# AVerCADE.net
KiCad netlist of a schematic drawn in EAGLE
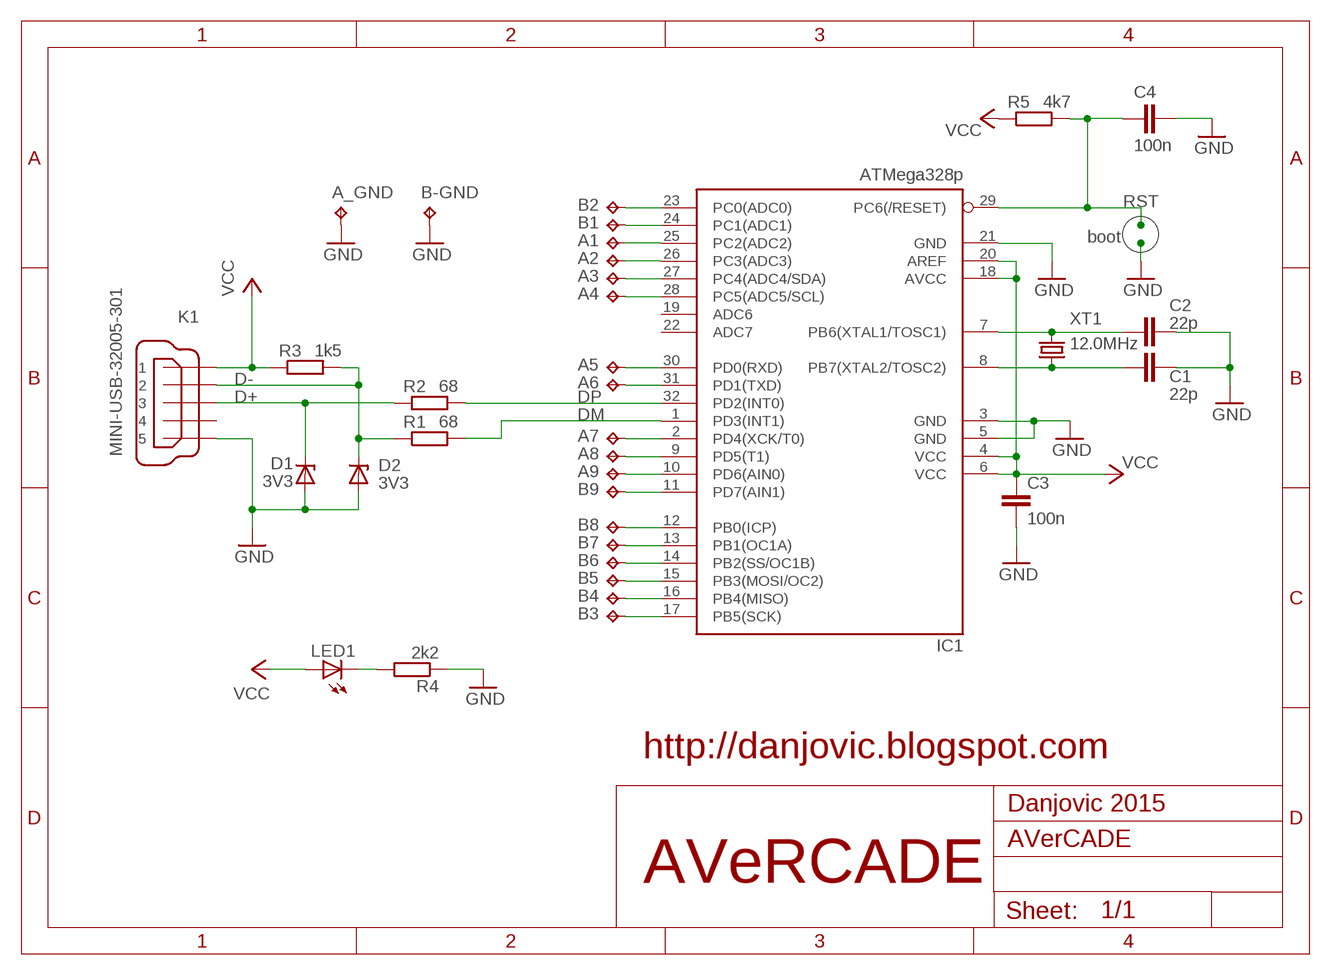
[diagram p0: schematic, sheet 1]

(export (version "E")
  (design (tool "Eeschema 10.0.6"))
  (components
    (comp (ref "A1")
      (value "TPPAD1-13")
      (footprint "eagle-import:P1-13")
      (libsource (lib "eagle-import") (part "TPPAD1-13"))
    )
    (comp (ref "A2")
      (value "TPPAD1-13")
      (footprint "eagle-import:P1-13")
      (libsource (lib "eagle-import") (part "TPPAD1-13"))
    )
    (comp (ref "A3")
      (value "TPPAD1-13")
      (footprint "eagle-import:P1-13")
      (libsource (lib "eagle-import") (part "TPPAD1-13"))
    )
    (comp (ref "A4")
      (value "TPPAD1-13")
      (footprint "eagle-import:P1-13")
      (libsource (lib "eagle-import") (part "TPPAD1-13"))
    )
    (comp (ref "A5")
      (value "TPPAD1-13")
      (footprint "eagle-import:P1-13")
      (libsource (lib "eagle-import") (part "TPPAD1-13"))
    )
    (comp (ref "A6")
      (value "TPPAD1-13")
      (footprint "eagle-import:P1-13")
      (libsource (lib "eagle-import") (part "TPPAD1-13"))
    )
    (comp (ref "A7")
      (value "TPPAD1-13")
      (footprint "eagle-import:P1-13")
      (libsource (lib "eagle-import") (part "TPPAD1-13"))
    )
    (comp (ref "A8")
      (value "TPPAD1-13")
      (footprint "eagle-import:P1-13")
      (libsource (lib "eagle-import") (part "TPPAD1-13"))
    )
    (comp (ref "A9")
      (value "TPPAD1-13")
      (footprint "eagle-import:P1-13")
      (libsource (lib "eagle-import") (part "TPPAD1-13"))
    )
    (comp (ref "A_GND")
      (value "TPPAD1-13")
      (footprint "eagle-import:P1-13")
      (libsource (lib "eagle-import") (part "TPPAD1-13"))
    )
    (comp (ref "B-GND")
      (value "TPPAD1-13")
      (footprint "eagle-import:P1-13")
      (libsource (lib "eagle-import") (part "TPPAD1-13"))
    )
    (comp (ref "B1")
      (value "TPPAD1-13")
      (footprint "eagle-import:P1-13")
      (libsource (lib "eagle-import") (part "TPPAD1-13"))
    )
    (comp (ref "B2")
      (value "TPPAD1-13")
      (footprint "eagle-import:P1-13")
      (libsource (lib "eagle-import") (part "TPPAD1-13"))
    )
    (comp (ref "B3")
      (value "TPPAD1-13")
      (footprint "eagle-import:P1-13")
      (libsource (lib "eagle-import") (part "TPPAD1-13"))
    )
    (comp (ref "B4")
      (value "TPPAD1-13")
      (footprint "eagle-import:P1-13")
      (libsource (lib "eagle-import") (part "TPPAD1-13"))
    )
    (comp (ref "B5")
      (value "TPPAD1-13")
      (footprint "eagle-import:P1-13")
      (libsource (lib "eagle-import") (part "TPPAD1-13"))
    )
    (comp (ref "B6")
      (value "TPPAD1-13")
      (footprint "eagle-import:P1-13")
      (libsource (lib "eagle-import") (part "TPPAD1-13"))
    )
    (comp (ref "B7")
      (value "TPPAD1-13")
      (footprint "eagle-import:P1-13")
      (libsource (lib "eagle-import") (part "TPPAD1-13"))
    )
    (comp (ref "B8")
      (value "TPPAD1-13")
      (footprint "eagle-import:P1-13")
      (libsource (lib "eagle-import") (part "TPPAD1-13"))
    )
    (comp (ref "B9")
      (value "TPPAD1-13")
      (footprint "eagle-import:P1-13")
      (libsource (lib "eagle-import") (part "TPPAD1-13"))
    )
    (comp (ref "C1")
      (value "22p")
      (footprint "eagle-import:C0805")
      (libsource (lib "eagle-import") (part "C-EUC0805"))
    )
    (comp (ref "C2")
      (value "22p")
      (footprint "eagle-import:C0805")
      (libsource (lib "eagle-import") (part "C-EUC0805"))
    )
    (comp (ref "C3")
      (value "100n")
      (footprint "eagle-import:C1206")
      (libsource (lib "eagle-import") (part "C-EUC1206"))
    )
    (comp (ref "C4")
      (value "100n")
      (footprint "eagle-import:C1206")
      (libsource (lib "eagle-import") (part "C-EUC1206"))
    )
    (comp (ref "D1")
      (value "3V3")
      (footprint "eagle-import:SOD80C")
      (libsource (lib "eagle-import") (part "ZENER-DIODESOD80C"))
    )
    (comp (ref "D2")
      (value "3V3")
      (footprint "eagle-import:SOD80C")
      (libsource (lib "eagle-import") (part "ZENER-DIODESOD80C"))
    )
    (comp (ref "IC1")
      (value "ATMega328p")
      (footprint "eagle-import:TQFP32-08")
      (fields (field (name "MPN") "ATMEGA8-16AU"))
      (libsource (lib "eagle-import") (part "MEGA8-AI"))
    )
    (comp (ref "K1")
      (value "MINI-USB-32005-301")
      (footprint "eagle-import:32005-301")
      (libsource (lib "eagle-import") (part "MINI-USB-32005-301"))
    )
    (comp (ref "LED1")
      (value "LEDSML1206")
      (footprint "eagle-import:SML1206")
      (libsource (lib "eagle-import") (part "LEDSML1206"))
    )
    (comp (ref "R1")
      (value "68")
      (footprint "eagle-import:M1206")
      (libsource (lib "eagle-import") (part "R-EU_M1206"))
    )
    (comp (ref "R2")
      (value "68")
      (footprint "eagle-import:M1206")
      (libsource (lib "eagle-import") (part "R-EU_M1206"))
    )
    (comp (ref "R3")
      (value "1k5")
      (footprint "eagle-import:M1206")
      (libsource (lib "eagle-import") (part "R-EU_M1206"))
    )
    (comp (ref "R4")
      (value "2k2")
      (footprint "eagle-import:M1206")
      (libsource (lib "eagle-import") (part "R-EU_M1206"))
    )
    (comp (ref "R5")
      (value "4k7")
      (footprint "eagle-import:M1206")
      (libsource (lib "eagle-import") (part "R-EU_M1206"))
    )
    (comp (ref "XT1")
      (value "12.0MHz")
      (footprint "eagle-import:HC49UP")
      (libsource (lib "eagle-import") (part "CRYSTALHC49UP"))
    )
  )
  (nets
    (net (code "1") (name "/D+") (class "Default")
      (node (ref "D1") (pin "C") (pinfunction "C_C") (pintype "passive"))
      (node (ref "K1") (pin "3") (pinfunction "3_3") (pintype "passive"))
      (node (ref "R2") (pin "1") (pinfunction "1_1") (pintype "passive"))
    )
    (net (code "2") (name "/D-") (class "Default")
      (node (ref "D2") (pin "C") (pinfunction "C_C") (pintype "passive"))
      (node (ref "K1") (pin "2") (pinfunction "2_2") (pintype "passive"))
      (node (ref "R1") (pin "1") (pinfunction "1_1") (pintype "passive"))
      (node (ref "R3") (pin "2") (pinfunction "2_2") (pintype "passive"))
    )
    (net (code "3") (name "/DM") (class "Default")
      (node (ref "IC1") (pin "1") (pinfunction "PD3(INT1)_1") (pintype "bidirectional"))
      (node (ref "R1") (pin "2") (pinfunction "2_2") (pintype "passive"))
    )
    (net (code "4") (name "/DP") (class "Default")
      (node (ref "IC1") (pin "32") (pinfunction "PD2(INT0)_32") (pintype "bidirectional"))
      (node (ref "R2") (pin "2") (pinfunction "2_2") (pintype "passive"))
    )
    (net (code "5") (name "/RST") (class "Default")
      (node (ref "C4") (pin "1") (pinfunction "1_1") (pintype "passive"))
      (node (ref "IC1") (pin "29") (pinfunction "PC6(/RESET)_29") (pintype "bidirectional"))
      (node (ref "R5") (pin "2") (pinfunction "2_2") (pintype "passive"))
    )
    (net (code "6") (name "GND") (class "Default")
      (node (ref "A_GND") (pin "TP") (pinfunction "TP_TP") (pintype "input"))
      (node (ref "B-GND") (pin "TP") (pinfunction "TP_TP") (pintype "input"))
      (node (ref "C1") (pin "2") (pinfunction "2_2") (pintype "passive"))
      (node (ref "C2") (pin "2") (pinfunction "2_2") (pintype "passive"))
      (node (ref "C3") (pin "2") (pinfunction "2_2") (pintype "passive"))
      (node (ref "C4") (pin "2") (pinfunction "2_2") (pintype "passive"))
      (node (ref "D1") (pin "A") (pinfunction "A_A") (pintype "passive"))
      (node (ref "D2") (pin "A") (pinfunction "A_A") (pintype "passive"))
      (node (ref "IC1") (pin "21") (pinfunction "GND_21") (pintype "power_in"))
      (node (ref "IC1") (pin "3") (pinfunction "GND_3") (pintype "power_in"))
      (node (ref "IC1") (pin "5") (pinfunction "GND_5") (pintype "power_in"))
      (node (ref "K1") (pin "5") (pinfunction "5_5") (pintype "passive"))
      (node (ref "R4") (pin "1") (pinfunction "1_1") (pintype "passive"))
    )
    (net (code "7") (name "Net-(IC1-PB0(ICP))") (class "Default")
      (node (ref "B8") (pin "TP") (pinfunction "TP_TP") (pintype "input"))
      (node (ref "IC1") (pin "12") (pinfunction "PB0(ICP)_12") (pintype "bidirectional"))
    )
    (net (code "8") (name "Net-(IC1-PB1(OC1A))") (class "Default")
      (node (ref "B7") (pin "TP") (pinfunction "TP_TP") (pintype "input"))
      (node (ref "IC1") (pin "13") (pinfunction "PB1(OC1A)_13") (pintype "bidirectional"))
    )
    (net (code "9") (name "Net-(IC1-PB2(SS{slash}OC1B))") (class "Default")
      (node (ref "B6") (pin "TP") (pinfunction "TP_TP") (pintype "input"))
      (node (ref "IC1") (pin "14") (pinfunction "PB2(SS/OC1B)_14") (pintype "bidirectional"))
    )
    (net (code "10") (name "Net-(IC1-PB3(MOSI{slash}OC2))") (class "Default")
      (node (ref "B5") (pin "TP") (pinfunction "TP_TP") (pintype "input"))
      (node (ref "IC1") (pin "15") (pinfunction "PB3(MOSI/OC2)_15") (pintype "bidirectional"))
    )
    (net (code "11") (name "Net-(IC1-PB4(MISO))") (class "Default")
      (node (ref "B4") (pin "TP") (pinfunction "TP_TP") (pintype "input"))
      (node (ref "IC1") (pin "16") (pinfunction "PB4(MISO)_16") (pintype "bidirectional"))
    )
    (net (code "12") (name "Net-(IC1-PB5(SCK))") (class "Default")
      (node (ref "B3") (pin "TP") (pinfunction "TP_TP") (pintype "input"))
      (node (ref "IC1") (pin "17") (pinfunction "PB5(SCK)_17") (pintype "bidirectional"))
    )
    (net (code "13") (name "Net-(IC1-PB6(XTAL1{slash}TOSC1))") (class "Default")
      (node (ref "C2") (pin "1") (pinfunction "1_1") (pintype "passive"))
      (node (ref "IC1") (pin "7") (pinfunction "PB6(XTAL1/TOSC1)_7") (pintype "bidirectional"))
      (node (ref "XT1") (pin "2") (pinfunction "2_2") (pintype "passive"))
    )
    (net (code "14") (name "Net-(IC1-PB7(XTAL2{slash}TOSC2))") (class "Default")
      (node (ref "C1") (pin "1") (pinfunction "1_1") (pintype "passive"))
      (node (ref "IC1") (pin "8") (pinfunction "PB7(XTAL2/TOSC2)_8") (pintype "bidirectional"))
      (node (ref "XT1") (pin "1") (pinfunction "1_1") (pintype "passive"))
    )
    (net (code "15") (name "Net-(IC1-PC0(ADC0))") (class "Default")
      (node (ref "B2") (pin "TP") (pinfunction "TP_TP") (pintype "input"))
      (node (ref "IC1") (pin "23") (pinfunction "PC0(ADC0)_23") (pintype "bidirectional"))
    )
    (net (code "16") (name "Net-(IC1-PC1(ADC1))") (class "Default")
      (node (ref "B1") (pin "TP") (pinfunction "TP_TP") (pintype "input"))
      (node (ref "IC1") (pin "24") (pinfunction "PC1(ADC1)_24") (pintype "bidirectional"))
    )
    (net (code "17") (name "Net-(IC1-PC2(ADC2))") (class "Default")
      (node (ref "A1") (pin "TP") (pinfunction "TP_TP") (pintype "input"))
      (node (ref "IC1") (pin "25") (pinfunction "PC2(ADC2)_25") (pintype "bidirectional"))
    )
    (net (code "18") (name "Net-(IC1-PC3(ADC3))") (class "Default")
      (node (ref "A2") (pin "TP") (pinfunction "TP_TP") (pintype "input"))
      (node (ref "IC1") (pin "26") (pinfunction "PC3(ADC3)_26") (pintype "bidirectional"))
    )
    (net (code "19") (name "Net-(IC1-PC4(ADC4{slash}SDA))") (class "Default")
      (node (ref "A3") (pin "TP") (pinfunction "TP_TP") (pintype "input"))
      (node (ref "IC1") (pin "27") (pinfunction "PC4(ADC4/SDA)_27") (pintype "bidirectional"))
    )
    (net (code "20") (name "Net-(IC1-PC5(ADC5{slash}SCL))") (class "Default")
      (node (ref "A4") (pin "TP") (pinfunction "TP_TP") (pintype "input"))
      (node (ref "IC1") (pin "28") (pinfunction "PC5(ADC5/SCL)_28") (pintype "bidirectional"))
    )
    (net (code "21") (name "Net-(IC1-PD0(RXD))") (class "Default")
      (node (ref "A5") (pin "TP") (pinfunction "TP_TP") (pintype "input"))
      (node (ref "IC1") (pin "30") (pinfunction "PD0(RXD)_30") (pintype "bidirectional"))
    )
    (net (code "22") (name "Net-(IC1-PD1(TXD))") (class "Default")
      (node (ref "A6") (pin "TP") (pinfunction "TP_TP") (pintype "input"))
      (node (ref "IC1") (pin "31") (pinfunction "PD1(TXD)_31") (pintype "bidirectional"))
    )
    (net (code "23") (name "Net-(IC1-PD4(XCK{slash}T0))") (class "Default")
      (node (ref "A7") (pin "TP") (pinfunction "TP_TP") (pintype "input"))
      (node (ref "IC1") (pin "2") (pinfunction "PD4(XCK/T0)_2") (pintype "bidirectional"))
    )
    (net (code "24") (name "Net-(IC1-PD5(T1))") (class "Default")
      (node (ref "A8") (pin "TP") (pinfunction "TP_TP") (pintype "input"))
      (node (ref "IC1") (pin "9") (pinfunction "PD5(T1)_9") (pintype "bidirectional"))
    )
    (net (code "25") (name "Net-(IC1-PD6(AIN0))") (class "Default")
      (node (ref "A9") (pin "TP") (pinfunction "TP_TP") (pintype "input"))
      (node (ref "IC1") (pin "10") (pinfunction "PD6(AIN0)_10") (pintype "bidirectional"))
    )
    (net (code "26") (name "Net-(IC1-PD7(AIN1))") (class "Default")
      (node (ref "B9") (pin "TP") (pinfunction "TP_TP") (pintype "input"))
      (node (ref "IC1") (pin "11") (pinfunction "PD7(AIN1)_11") (pintype "bidirectional"))
    )
    (net (code "27") (name "Net-(LED1-PadC)") (class "Default")
      (node (ref "LED1") (pin "C") (pinfunction "C_C") (pintype "passive"))
      (node (ref "R4") (pin "2") (pinfunction "2_2") (pintype "passive"))
    )
    (net (code "28") (name "VCC") (class "Default")
      (node (ref "C3") (pin "1") (pinfunction "1_1") (pintype "passive"))
      (node (ref "IC1") (pin "18") (pinfunction "AVCC_18") (pintype "power_in"))
      (node (ref "IC1") (pin "20") (pinfunction "AREF_20") (pintype "passive"))
      (node (ref "IC1") (pin "4") (pinfunction "VCC_4") (pintype "power_in"))
      (node (ref "IC1") (pin "6") (pinfunction "VCC_6") (pintype "power_in"))
      (node (ref "K1") (pin "1") (pinfunction "1_1") (pintype "passive"))
      (node (ref "LED1") (pin "A") (pinfunction "A_A") (pintype "passive"))
      (node (ref "R3") (pin "1") (pinfunction "1_1") (pintype "passive"))
      (node (ref "R5") (pin "1") (pinfunction "1_1") (pintype "passive"))
    )
    (net (code "29") (name "unconnected-(IC1-ADC6-Pad19)") (class "Default")
      (node (ref "IC1") (pin "19") (pinfunction "ADC6_19") (pintype "bidirectional"))
    )
    (net (code "30") (name "unconnected-(IC1-ADC7-Pad22)") (class "Default")
      (node (ref "IC1") (pin "22") (pinfunction "ADC7_22") (pintype "bidirectional"))
    )
    (net (code "31") (name "unconnected-(K1-Pad4)") (class "Default")
      (node (ref "K1") (pin "4") (pinfunction "4_4") (pintype "passive"))
    )
  )
)
